# RSD_M1_LED_TURN_RIGHT_V2.net
KiCad netlist of a schematic drawn in Altium Designer
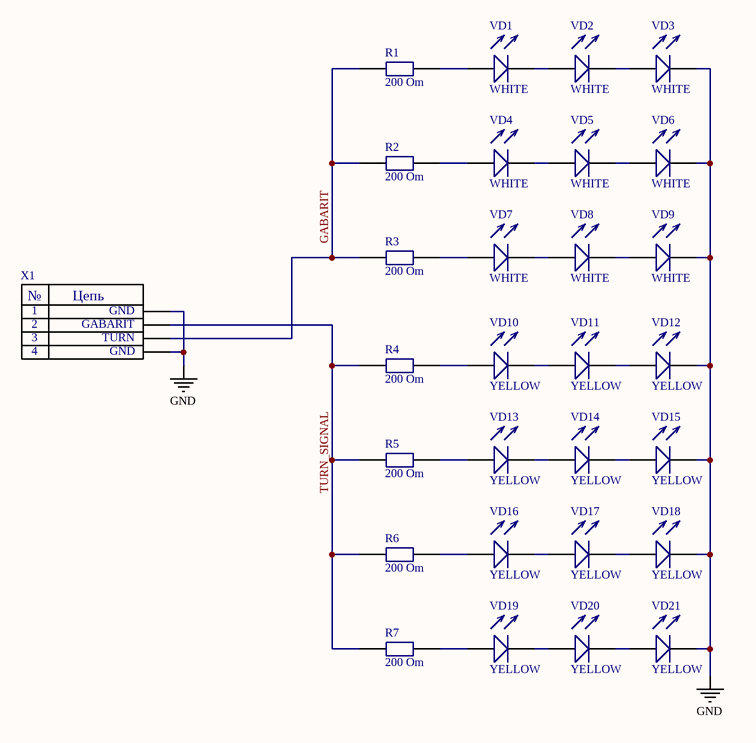
[diagram p0: RSD_M1_LED_TURN_RIGHT_V2.SchDoc]

(export (version "E")
  (design (tool "Eeschema 10.0.6"))
  (components
    (comp (ref "R1")
      (value "200 Om")
      (footprint "Res0603")
      (fields (field (name "Comment") "Resistor"))
      (libsource (lib "my_library") (part "Resistor"))
    )
    (comp (ref "R2")
      (value "200 Om")
      (footprint "Res0603")
      (fields (field (name "Comment") "Resistor"))
      (libsource (lib "my_library") (part "Resistor"))
    )
    (comp (ref "R3")
      (value "200 Om")
      (footprint "Res0603")
      (fields (field (name "Comment") "Resistor"))
      (libsource (lib "my_library") (part "Resistor"))
    )
    (comp (ref "R4")
      (value "200 Om")
      (footprint "Res0603")
      (fields (field (name "Comment") "Resistor"))
      (libsource (lib "my_library") (part "Resistor"))
    )
    (comp (ref "R5")
      (value "200 Om")
      (footprint "Res0603")
      (fields (field (name "Comment") "Resistor"))
      (libsource (lib "my_library") (part "Resistor"))
    )
    (comp (ref "R6")
      (value "200 Om")
      (footprint "Res0603")
      (fields (field (name "Comment") "Resistor"))
      (libsource (lib "my_library") (part "Resistor"))
    )
    (comp (ref "R7")
      (value "200 Om")
      (footprint "Res0603")
      (fields (field (name "Comment") "Resistor"))
      (libsource (lib "my_library") (part "Resistor"))
    )
    (comp (ref "VD1")
      (value "WHITE")
      (footprint "3528_LED")
      (fields (field (name "Comment") "LED"))
      (libsource (lib "my_library") (part "LED"))
    )
    (comp (ref "VD2")
      (value "WHITE")
      (footprint "3528_LED")
      (fields (field (name "Comment") "LED"))
      (libsource (lib "my_library") (part "LED"))
    )
    (comp (ref "VD3")
      (value "WHITE")
      (footprint "3528_LED")
      (fields (field (name "Comment") "LED"))
      (libsource (lib "my_library") (part "LED"))
    )
    (comp (ref "VD4")
      (value "WHITE")
      (footprint "3528_LED")
      (fields (field (name "Comment") "LED"))
      (libsource (lib "my_library") (part "LED"))
    )
    (comp (ref "VD5")
      (value "WHITE")
      (footprint "3528_LED")
      (fields (field (name "Comment") "LED"))
      (libsource (lib "my_library") (part "LED"))
    )
    (comp (ref "VD6")
      (value "WHITE")
      (footprint "3528_LED")
      (fields (field (name "Comment") "LED"))
      (libsource (lib "my_library") (part "LED"))
    )
    (comp (ref "VD7")
      (value "WHITE")
      (footprint "3528_LED")
      (fields (field (name "Comment") "LED"))
      (libsource (lib "my_library") (part "LED"))
    )
    (comp (ref "VD8")
      (value "WHITE")
      (footprint "3528_LED")
      (fields (field (name "Comment") "LED"))
      (libsource (lib "my_library") (part "LED"))
    )
    (comp (ref "VD9")
      (value "WHITE")
      (footprint "3528_LED")
      (fields (field (name "Comment") "LED"))
      (libsource (lib "my_library") (part "LED"))
    )
    (comp (ref "VD10")
      (value "YELLOW")
      (footprint "3528_LED")
      (fields (field (name "Comment") "LED"))
      (libsource (lib "my_library") (part "LED"))
    )
    (comp (ref "VD11")
      (value "YELLOW")
      (footprint "3528_LED")
      (fields (field (name "Comment") "LED"))
      (libsource (lib "my_library") (part "LED"))
    )
    (comp (ref "VD12")
      (value "YELLOW")
      (footprint "3528_LED")
      (fields (field (name "Comment") "LED"))
      (libsource (lib "my_library") (part "LED"))
    )
    (comp (ref "VD13")
      (value "YELLOW")
      (footprint "3528_LED")
      (fields (field (name "Comment") "LED"))
      (libsource (lib "my_library") (part "LED"))
    )
    (comp (ref "VD14")
      (value "YELLOW")
      (footprint "3528_LED")
      (fields (field (name "Comment") "LED"))
      (libsource (lib "my_library") (part "LED"))
    )
    (comp (ref "VD15")
      (value "YELLOW")
      (footprint "3528_LED")
      (fields (field (name "Comment") "LED"))
      (libsource (lib "my_library") (part "LED"))
    )
    (comp (ref "VD16")
      (value "YELLOW")
      (footprint "3528_LED")
      (fields (field (name "Comment") "LED"))
      (libsource (lib "my_library") (part "LED"))
    )
    (comp (ref "VD17")
      (value "YELLOW")
      (footprint "3528_LED")
      (fields (field (name "Comment") "LED"))
      (libsource (lib "my_library") (part "LED"))
    )
    (comp (ref "VD18")
      (value "YELLOW")
      (footprint "3528_LED")
      (fields (field (name "Comment") "LED"))
      (libsource (lib "my_library") (part "LED"))
    )
    (comp (ref "VD19")
      (value "YELLOW")
      (footprint "3528_LED")
      (fields (field (name "Comment") "LED"))
      (libsource (lib "my_library") (part "LED"))
    )
    (comp (ref "VD20")
      (value "YELLOW")
      (footprint "3528_LED")
      (fields (field (name "Comment") "LED"))
      (libsource (lib "my_library") (part "LED"))
    )
    (comp (ref "VD21")
      (value "YELLOW")
      (footprint "3528_LED")
      (fields (field (name "Comment") "LED"))
      (libsource (lib "my_library") (part "LED"))
    )
    (comp (ref "X1")
      (value "FPC_connector_4_1")
      (footprint "FPC_4_1")
      (fields
        (field (name "1") "GND")
        (field (name "2") "GABARIT")
        (field (name "3") "TURN")
        (field (name "4") "GND")
      )
      (libsource (lib "my_library") (part "FPC_connector_4_1"))
    )
  )
  (nets
    (net (code "1") (name "/GABARIT") (class "Default")
      (node (ref "R1") (pin "2") (pinfunction "2_2") (pintype "passive"))
      (node (ref "R2") (pin "2") (pinfunction "2_2") (pintype "passive"))
      (node (ref "R3") (pin "2") (pinfunction "2_2") (pintype "passive"))
      (node (ref "X1") (pin "3") (pinfunction "3_3") (pintype "passive"))
    )
    (net (code "2") (name "/TURN_SIGNAL") (class "Default")
      (node (ref "R4") (pin "2") (pinfunction "2_2") (pintype "passive"))
      (node (ref "R5") (pin "2") (pinfunction "2_2") (pintype "passive"))
      (node (ref "R6") (pin "2") (pinfunction "2_2") (pintype "passive"))
      (node (ref "R7") (pin "2") (pinfunction "2_2") (pintype "passive"))
      (node (ref "X1") (pin "2") (pinfunction "2_2") (pintype "passive"))
    )
    (net (code "3") (name "GND") (class "Default")
      (node (ref "VD12") (pin "1") (pinfunction "1_1") (pintype "passive"))
      (node (ref "VD15") (pin "1") (pinfunction "1_1") (pintype "passive"))
      (node (ref "VD18") (pin "1") (pinfunction "1_1") (pintype "passive"))
      (node (ref "VD21") (pin "1") (pinfunction "1_1") (pintype "passive"))
      (node (ref "VD3") (pin "1") (pinfunction "1_1") (pintype "passive"))
      (node (ref "VD6") (pin "1") (pinfunction "1_1") (pintype "passive"))
      (node (ref "VD9") (pin "1") (pinfunction "1_1") (pintype "passive"))
      (node (ref "X1") (pin "1") (pinfunction "1_1") (pintype "passive"))
      (node (ref "X1") (pin "4") (pinfunction "4_4") (pintype "passive"))
    )
    (net (code "4") (name "Net-(R1-Pad1)") (class "Default")
      (node (ref "R1") (pin "1") (pinfunction "1_1") (pintype "passive"))
      (node (ref "VD1") (pin "2") (pinfunction "2_2") (pintype "passive"))
    )
    (net (code "5") (name "Net-(R2-Pad1)") (class "Default")
      (node (ref "R2") (pin "1") (pinfunction "1_1") (pintype "passive"))
      (node (ref "VD4") (pin "2") (pinfunction "2_2") (pintype "passive"))
    )
    (net (code "6") (name "Net-(R3-Pad1)") (class "Default")
      (node (ref "R3") (pin "1") (pinfunction "1_1") (pintype "passive"))
      (node (ref "VD7") (pin "2") (pinfunction "2_2") (pintype "passive"))
    )
    (net (code "7") (name "Net-(R4-Pad1)") (class "Default")
      (node (ref "R4") (pin "1") (pinfunction "1_1") (pintype "passive"))
      (node (ref "VD10") (pin "2") (pinfunction "2_2") (pintype "passive"))
    )
    (net (code "8") (name "Net-(R5-Pad1)") (class "Default")
      (node (ref "R5") (pin "1") (pinfunction "1_1") (pintype "passive"))
      (node (ref "VD13") (pin "2") (pinfunction "2_2") (pintype "passive"))
    )
    (net (code "9") (name "Net-(R6-Pad1)") (class "Default")
      (node (ref "R6") (pin "1") (pinfunction "1_1") (pintype "passive"))
      (node (ref "VD16") (pin "2") (pinfunction "2_2") (pintype "passive"))
    )
    (net (code "10") (name "Net-(R7-Pad1)") (class "Default")
      (node (ref "R7") (pin "1") (pinfunction "1_1") (pintype "passive"))
      (node (ref "VD19") (pin "2") (pinfunction "2_2") (pintype "passive"))
    )
    (net (code "11") (name "Net-(VD1-Pad1)") (class "Default")
      (node (ref "VD1") (pin "1") (pinfunction "1_1") (pintype "passive"))
      (node (ref "VD2") (pin "2") (pinfunction "2_2") (pintype "passive"))
    )
    (net (code "12") (name "Net-(VD2-Pad1)") (class "Default")
      (node (ref "VD2") (pin "1") (pinfunction "1_1") (pintype "passive"))
      (node (ref "VD3") (pin "2") (pinfunction "2_2") (pintype "passive"))
    )
    (net (code "13") (name "Net-(VD4-Pad1)") (class "Default")
      (node (ref "VD4") (pin "1") (pinfunction "1_1") (pintype "passive"))
      (node (ref "VD5") (pin "2") (pinfunction "2_2") (pintype "passive"))
    )
    (net (code "14") (name "Net-(VD5-Pad1)") (class "Default")
      (node (ref "VD5") (pin "1") (pinfunction "1_1") (pintype "passive"))
      (node (ref "VD6") (pin "2") (pinfunction "2_2") (pintype "passive"))
    )
    (net (code "15") (name "Net-(VD7-Pad1)") (class "Default")
      (node (ref "VD7") (pin "1") (pinfunction "1_1") (pintype "passive"))
      (node (ref "VD8") (pin "2") (pinfunction "2_2") (pintype "passive"))
    )
    (net (code "16") (name "Net-(VD8-Pad1)") (class "Default")
      (node (ref "VD8") (pin "1") (pinfunction "1_1") (pintype "passive"))
      (node (ref "VD9") (pin "2") (pinfunction "2_2") (pintype "passive"))
    )
    (net (code "17") (name "Net-(VD10-Pad1)") (class "Default")
      (node (ref "VD10") (pin "1") (pinfunction "1_1") (pintype "passive"))
      (node (ref "VD11") (pin "2") (pinfunction "2_2") (pintype "passive"))
    )
    (net (code "18") (name "Net-(VD11-Pad1)") (class "Default")
      (node (ref "VD11") (pin "1") (pinfunction "1_1") (pintype "passive"))
      (node (ref "VD12") (pin "2") (pinfunction "2_2") (pintype "passive"))
    )
    (net (code "19") (name "Net-(VD13-Pad1)") (class "Default")
      (node (ref "VD13") (pin "1") (pinfunction "1_1") (pintype "passive"))
      (node (ref "VD14") (pin "2") (pinfunction "2_2") (pintype "passive"))
    )
    (net (code "20") (name "Net-(VD14-Pad1)") (class "Default")
      (node (ref "VD14") (pin "1") (pinfunction "1_1") (pintype "passive"))
      (node (ref "VD15") (pin "2") (pinfunction "2_2") (pintype "passive"))
    )
    (net (code "21") (name "Net-(VD16-Pad1)") (class "Default")
      (node (ref "VD16") (pin "1") (pinfunction "1_1") (pintype "passive"))
      (node (ref "VD17") (pin "2") (pinfunction "2_2") (pintype "passive"))
    )
    (net (code "22") (name "Net-(VD17-Pad1)") (class "Default")
      (node (ref "VD17") (pin "1") (pinfunction "1_1") (pintype "passive"))
      (node (ref "VD18") (pin "2") (pinfunction "2_2") (pintype "passive"))
    )
    (net (code "23") (name "Net-(VD19-Pad1)") (class "Default")
      (node (ref "VD19") (pin "1") (pinfunction "1_1") (pintype "passive"))
      (node (ref "VD20") (pin "2") (pinfunction "2_2") (pintype "passive"))
    )
    (net (code "24") (name "Net-(VD20-Pad1)") (class "Default")
      (node (ref "VD20") (pin "1") (pinfunction "1_1") (pintype "passive"))
      (node (ref "VD21") (pin "2") (pinfunction "2_2") (pintype "passive"))
    )
  )
)
